# sensor_28mm_circle.net
KiCad netlist of a schematic drawn in EAGLE
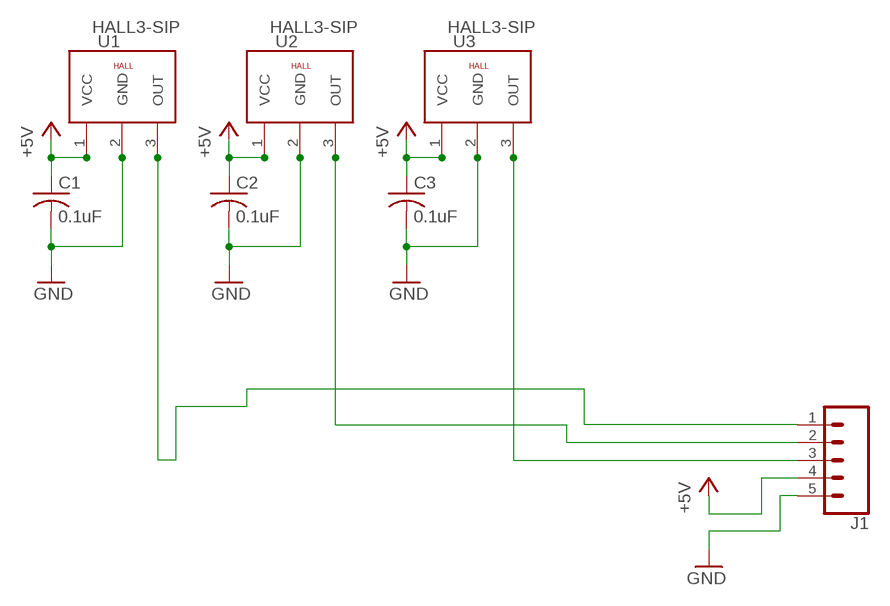
[diagram p0: schematic, sheet 1]

(export (version "E")
  (design (tool "Eeschema 10.0.6"))
  (components
    (comp (ref "C1")
      (value "0.1uF")
      (footprint "eagle-import:C0603")
      (libsource (lib "eagle-import") (part "C-USC0603"))
    )
    (comp (ref "C2")
      (value "0.1uF")
      (footprint "eagle-import:C0603")
      (libsource (lib "eagle-import") (part "C-USC0603"))
    )
    (comp (ref "C3")
      (value "0.1uF")
      (footprint "eagle-import:C0603")
      (libsource (lib "eagle-import") (part "C-USC0603"))
    )
    (comp (ref "J1")
      (value "CONN_05PTH_LONGPADS")
      (footprint "eagle-import:1X05_LONGPADS")
      (libsource (lib "eagle-import") (part "CONN_05PTH_LONGPADS"))
    )
    (comp (ref "U1")
      (value "HALL3-SIP")
      (footprint "eagle-import:3PINS1,27")
      (libsource (lib "eagle-import") (part "HALL3-SIP"))
    )
    (comp (ref "U2")
      (value "HALL3-SIP")
      (footprint "eagle-import:3PINS1,27")
      (libsource (lib "eagle-import") (part "HALL3-SIP"))
    )
    (comp (ref "U3")
      (value "HALL3-SIP")
      (footprint "eagle-import:3PINS1,27")
      (libsource (lib "eagle-import") (part "HALL3-SIP"))
    )
  )
  (nets
    (net (code "1") (name "+5V") (class "Default")
      (node (ref "C1") (pin "1") (pinfunction "1_1") (pintype "passive"))
      (node (ref "C2") (pin "1") (pinfunction "1_1") (pintype "passive"))
      (node (ref "C3") (pin "1") (pinfunction "1_1") (pintype "passive"))
      (node (ref "J1") (pin "4") (pinfunction "4_4") (pintype "passive"))
      (node (ref "U1") (pin "1") (pinfunction "VCC_1") (pintype "bidirectional"))
      (node (ref "U2") (pin "1") (pinfunction "VCC_1") (pintype "bidirectional"))
      (node (ref "U3") (pin "1") (pinfunction "VCC_1") (pintype "bidirectional"))
    )
    (net (code "2") (name "GND") (class "Default")
      (node (ref "C1") (pin "2") (pinfunction "2_2") (pintype "passive"))
      (node (ref "C2") (pin "2") (pinfunction "2_2") (pintype "passive"))
      (node (ref "C3") (pin "2") (pinfunction "2_2") (pintype "passive"))
      (node (ref "J1") (pin "5") (pinfunction "5_5") (pintype "passive"))
      (node (ref "U1") (pin "2") (pinfunction "GND_2") (pintype "bidirectional"))
      (node (ref "U2") (pin "2") (pinfunction "GND_2") (pintype "bidirectional"))
      (node (ref "U3") (pin "2") (pinfunction "GND_2") (pintype "bidirectional"))
    )
    (net (code "3") (name "Net-(U1-OUT)") (class "Default")
      (node (ref "J1") (pin "1") (pinfunction "1_1") (pintype "passive"))
      (node (ref "U1") (pin "3") (pinfunction "OUT_3") (pintype "bidirectional"))
    )
    (net (code "4") (name "Net-(U2-OUT)") (class "Default")
      (node (ref "J1") (pin "2") (pinfunction "2_2") (pintype "passive"))
      (node (ref "U2") (pin "3") (pinfunction "OUT_3") (pintype "bidirectional"))
    )
    (net (code "5") (name "Net-(U3-OUT)") (class "Default")
      (node (ref "J1") (pin "3") (pinfunction "3_3") (pintype "passive"))
      (node (ref "U3") (pin "3") (pinfunction "OUT_3") (pintype "bidirectional"))
    )
  )
)
